# rk86-psu.net
KiCad netlist of a schematic drawn in EAGLE
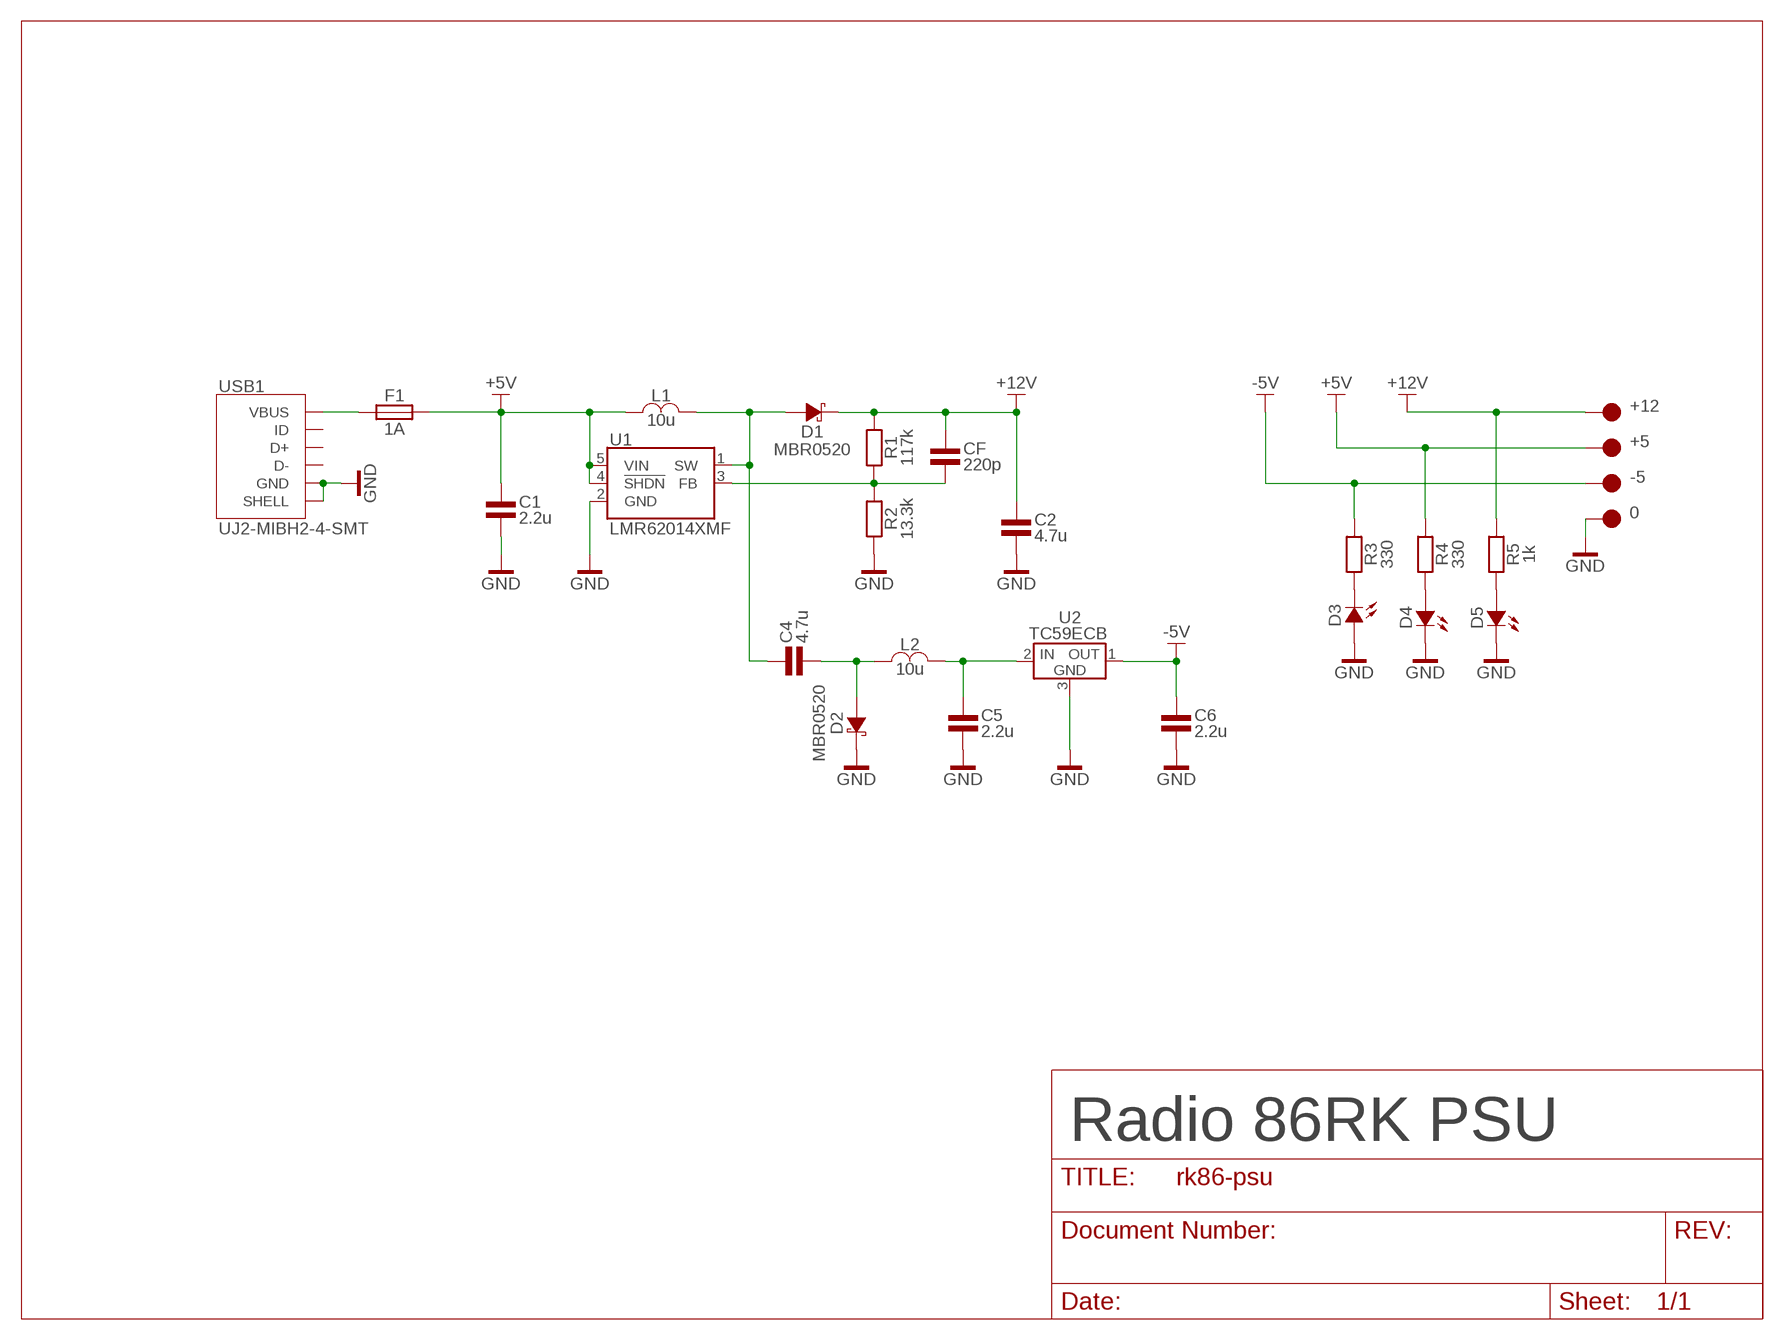
[diagram p0: schematic, sheet 1]

(export (version "E")
  (design (tool "Eeschema 10.0.6"))
  (components
    (comp (ref "+5")
      (value "WIREPAD_BOX")
      (footprint "eagle-import:WIREPAD_BOX")
      (libsource (lib "eagle-import") (part "WIREPAD_BOX"))
    )
    (comp (ref "+12")
      (value "WIREPAD_BOX")
      (footprint "eagle-import:WIREPAD_BOX")
      (libsource (lib "eagle-import") (part "WIREPAD_BOX"))
    )
    (comp (ref "-5")
      (value "WIREPAD_BOX")
      (footprint "eagle-import:WIREPAD_BOX")
      (libsource (lib "eagle-import") (part "WIREPAD_BOX"))
    )
    (comp (ref "0")
      (value "WIREPAD_BOX")
      (footprint "eagle-import:WIREPAD_BOX")
      (libsource (lib "eagle-import") (part "WIREPAD_BOX"))
    )
    (comp (ref "C1")
      (value "2.2u")
      (footprint "eagle-import:1206")
      (libsource (lib "eagle-import") (part "CAPACITOR_SMD1206"))
    )
    (comp (ref "C2")
      (value "4.7u")
      (footprint "eagle-import:1206")
      (libsource (lib "eagle-import") (part "CAPACITOR_SMD1206"))
    )
    (comp (ref "C4")
      (value "4.7u")
      (footprint "eagle-import:1206")
      (libsource (lib "eagle-import") (part "CAPACITOR_SMD1206"))
    )
    (comp (ref "C5")
      (value "2.2u")
      (footprint "eagle-import:1206")
      (libsource (lib "eagle-import") (part "CAPACITOR_SMD1206"))
    )
    (comp (ref "C6")
      (value "2.2u")
      (footprint "eagle-import:1206")
      (libsource (lib "eagle-import") (part "CAPACITOR_SMD1206"))
    )
    (comp (ref "CF")
      (value "220p")
      (footprint "eagle-import:0805")
      (libsource (lib "eagle-import") (part "CAPACITOR_SMD0805"))
    )
    (comp (ref "D1")
      (value "MBR0520")
      (footprint "eagle-import:SOD123")
      (libsource (lib "eagle-import") (part "MBR0520"))
    )
    (comp (ref "D2")
      (value "MBR0520")
      (footprint "eagle-import:SOD123")
      (libsource (lib "eagle-import") (part "MBR0520"))
    )
    (comp (ref "D3")
      (value "LED0805")
      (footprint "eagle-import:0805POL")
      (libsource (lib "eagle-import") (part "LED0805"))
    )
    (comp (ref "D4")
      (value "LED0805")
      (footprint "eagle-import:0805POL")
      (libsource (lib "eagle-import") (part "LED0805"))
    )
    (comp (ref "D5")
      (value "LED0805")
      (footprint "eagle-import:0805POL")
      (libsource (lib "eagle-import") (part "LED0805"))
    )
    (comp (ref "F1")
      (value "1A")
      (footprint "eagle-import:1812")
      (libsource (lib "eagle-import") (part "FUSE1812"))
    )
    (comp (ref "L1")
      (value "10u")
      (footprint "eagle-import:BOUNRNS_SRN6045TA")
      (libsource (lib "eagle-import") (part "INDUCTOR_FIXEDSRN6045TA"))
    )
    (comp (ref "L2")
      (value "10u")
      (footprint "eagle-import:BOUNRNS_SRN6045TA")
      (libsource (lib "eagle-import") (part "INDUCTOR_FIXEDSRN6045TA"))
    )
    (comp (ref "R1")
      (value "117k")
      (footprint "eagle-import:0805")
      (libsource (lib "eagle-import") (part "RESISTOR0805"))
    )
    (comp (ref "R2")
      (value "13.3k")
      (footprint "eagle-import:0805")
      (libsource (lib "eagle-import") (part "RESISTOR0805"))
    )
    (comp (ref "R3")
      (value "330")
      (footprint "eagle-import:0805")
      (libsource (lib "eagle-import") (part "RESISTOR0805"))
    )
    (comp (ref "R4")
      (value "330")
      (footprint "eagle-import:0805")
      (libsource (lib "eagle-import") (part "RESISTOR0805"))
    )
    (comp (ref "R5")
      (value "1k")
      (footprint "eagle-import:0805")
      (libsource (lib "eagle-import") (part "RESISTOR0805"))
    )
    (comp (ref "U1")
      (value "LMR62014XMF")
      (footprint "eagle-import:SOT23-5")
      (libsource (lib "eagle-import") (part "LMR62014XMF"))
    )
    (comp (ref "U2")
      (value "TC59ECB")
      (footprint "eagle-import:SOT23-3")
      (libsource (lib "eagle-import") (part "TC59ECB"))
    )
    (comp (ref "USB1")
      (value "UJ2-MIBH2-4-SMT")
      (footprint "eagle-import:UJ2-MIBH2-4-SMT")
      (libsource (lib "eagle-import") (part "USBUJ2-MIBH2-4-SMT"))
    )
  )
  (nets
    (net (code "1") (name "+5V") (class "Default")
      (node (ref "+5") (pin "P$1") (pinfunction "P$1_P$1") (pintype "passive"))
      (node (ref "C1") (pin "2") (pinfunction "P$2_2") (pintype "passive"))
      (node (ref "F1") (pin "P$2") (pinfunction "P$2_P$2") (pintype "passive"))
      (node (ref "L1") (pin "P$1") (pinfunction "P$1_P$1") (pintype "passive"))
      (node (ref "R4") (pin "2") (pinfunction "P$2_2") (pintype "passive"))
      (node (ref "U1") (pin "4") (pinfunction "~{SHDN}_4") (pintype "input"))
      (node (ref "U1") (pin "5") (pinfunction "VIN_5") (pintype "input"))
    )
    (net (code "2") (name "+12V") (class "Default")
      (node (ref "+12") (pin "P$1") (pinfunction "P$1_P$1") (pintype "passive"))
      (node (ref "C2") (pin "2") (pinfunction "P$2_2") (pintype "passive"))
      (node (ref "CF") (pin "2") (pinfunction "P$2_2") (pintype "passive"))
      (node (ref "D1") (pin "K") (pinfunction "K_K") (pintype "passive"))
      (node (ref "R1") (pin "2") (pinfunction "P$2_2") (pintype "passive"))
      (node (ref "R5") (pin "2") (pinfunction "P$2_2") (pintype "passive"))
    )
    (net (code "3") (name "-5V") (class "Default")
      (node (ref "-5") (pin "P$1") (pinfunction "P$1_P$1") (pintype "passive"))
      (node (ref "C6") (pin "2") (pinfunction "P$2_2") (pintype "passive"))
      (node (ref "R3") (pin "2") (pinfunction "P$2_2") (pintype "passive"))
      (node (ref "U2") (pin "1") (pinfunction "OUT_1") (pintype "passive"))
    )
    (net (code "4") (name "GND") (class "Default")
      (node (ref "0") (pin "P$1") (pinfunction "P$1_P$1") (pintype "passive"))
      (node (ref "C1") (pin "1") (pinfunction "P$1_1") (pintype "passive"))
      (node (ref "C2") (pin "1") (pinfunction "P$1_1") (pintype "passive"))
      (node (ref "C5") (pin "1") (pinfunction "P$1_1") (pintype "passive"))
      (node (ref "C6") (pin "1") (pinfunction "P$1_1") (pintype "passive"))
      (node (ref "D2") (pin "K") (pinfunction "K_K") (pintype "passive"))
      (node (ref "D3") (pin "A") (pinfunction "A_A") (pintype "passive"))
      (node (ref "D4") (pin "K") (pinfunction "K_K") (pintype "passive"))
      (node (ref "D5") (pin "K") (pinfunction "K_K") (pintype "passive"))
      (node (ref "R2") (pin "1") (pinfunction "P$1_1") (pintype "passive"))
      (node (ref "U1") (pin "2") (pinfunction "GND_2") (pintype "power_in"))
      (node (ref "U2") (pin "3") (pinfunction "GND_3") (pintype "power_in"))
      (node (ref "USB1") (pin "5") (pinfunction "GND_5") (pintype "passive"))
      (node (ref "USB1") (pin "S1") (pinfunction "SHELL_S1") (pintype "passive"))
      (node (ref "USB1") (pin "S2") (pinfunction "SHELL_S2") (pintype "passive"))
      (node (ref "USB1") (pin "S3") (pinfunction "SHELL_S3") (pintype "passive"))
      (node (ref "USB1") (pin "S4") (pinfunction "SHELL_S4") (pintype "passive"))
      (node (ref "USB1") (pin "S5") (pinfunction "SHELL_S5") (pintype "passive"))
    )
    (net (code "5") (name "Net-(C4-P$1)") (class "Default")
      (node (ref "C4") (pin "1") (pinfunction "P$1_1") (pintype "passive"))
      (node (ref "D2") (pin "A") (pinfunction "A_A") (pintype "passive"))
      (node (ref "L2") (pin "P$1") (pinfunction "P$1_P$1") (pintype "passive"))
    )
    (net (code "6") (name "Net-(C4-P$2)") (class "Default")
      (node (ref "C4") (pin "2") (pinfunction "P$2_2") (pintype "passive"))
      (node (ref "D1") (pin "A") (pinfunction "A_A") (pintype "passive"))
      (node (ref "L1") (pin "P$2") (pinfunction "P$2_P$2") (pintype "passive"))
      (node (ref "U1") (pin "1") (pinfunction "SW_1") (pintype "passive"))
    )
    (net (code "7") (name "Net-(C5-P$2)") (class "Default")
      (node (ref "C5") (pin "2") (pinfunction "P$2_2") (pintype "passive"))
      (node (ref "L2") (pin "P$2") (pinfunction "P$2_P$2") (pintype "passive"))
      (node (ref "U2") (pin "2") (pinfunction "IN_2") (pintype "input"))
    )
    (net (code "8") (name "Net-(CF-P$1)") (class "Default")
      (node (ref "CF") (pin "1") (pinfunction "P$1_1") (pintype "passive"))
      (node (ref "R1") (pin "1") (pinfunction "P$1_1") (pintype "passive"))
      (node (ref "R2") (pin "2") (pinfunction "P$2_2") (pintype "passive"))
      (node (ref "U1") (pin "3") (pinfunction "FB_3") (pintype "input"))
    )
    (net (code "9") (name "Net-(R3-P$1)") (class "Default")
      (node (ref "D3") (pin "K") (pinfunction "K_K") (pintype "passive"))
      (node (ref "R3") (pin "1") (pinfunction "P$1_1") (pintype "passive"))
    )
    (net (code "10") (name "Net-(R4-P$1)") (class "Default")
      (node (ref "D4") (pin "A") (pinfunction "A_A") (pintype "passive"))
      (node (ref "R4") (pin "1") (pinfunction "P$1_1") (pintype "passive"))
    )
    (net (code "11") (name "Net-(R5-P$1)") (class "Default")
      (node (ref "D5") (pin "A") (pinfunction "A_A") (pintype "passive"))
      (node (ref "R5") (pin "1") (pinfunction "P$1_1") (pintype "passive"))
    )
    (net (code "12") (name "Net-(USB1-VBUS)") (class "Default")
      (node (ref "F1") (pin "P$1") (pinfunction "P$1_P$1") (pintype "passive"))
      (node (ref "USB1") (pin "1") (pinfunction "VBUS_1") (pintype "passive"))
    )
    (net (code "13") (name "unconnected-(USB1-D+-Pad3)") (class "Default")
      (node (ref "USB1") (pin "3") (pinfunction "D+_3") (pintype "passive"))
    )
    (net (code "14") (name "unconnected-(USB1-D--Pad2)") (class "Default")
      (node (ref "USB1") (pin "2") (pinfunction "D-_2") (pintype "passive"))
    )
    (net (code "15") (name "unconnected-(USB1-ID-Pad4)") (class "Default")
      (node (ref "USB1") (pin "4") (pinfunction "ID_4") (pintype "passive"))
    )
  )
)
